# LightSwitch.net
KiCad netlist of a schematic drawn in EAGLE
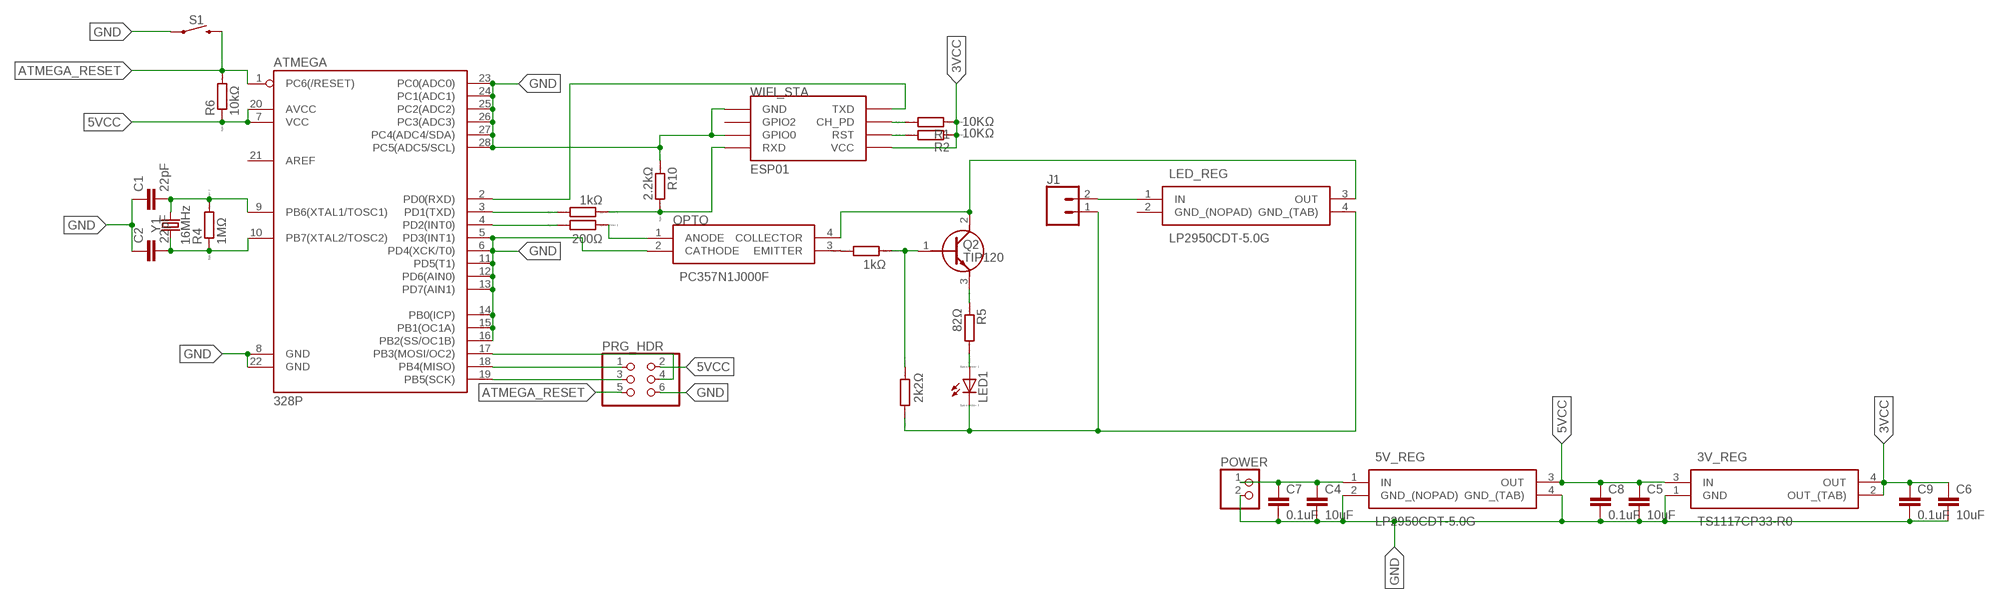
[diagram p0: schematic, sheet 1]

(export (version "E")
  (design (tool "Eeschema 10.0.6"))
  (components
    (comp (ref "3V_REG")
      (value "TS1117CP33-R0")
      (footprint "eagle-import:TO229P990X238-4N")
      (fields
        (field (name "MANUFACTURER_PART_NUMBER") "LP2950CDT-5.0G")
        (field (name "MOUSER_PART_NUMBER") "863-LP2950CDT-5.0G")
        (field (name "RS_PART_NUMBER") "0463593P")
      )
      (libsource (lib "eagle-import") (part "TS1117CP33-R0"))
    )
    (comp (ref "5V_REG")
      (value "LP2950CDT-5.0G")
      (footprint "eagle-import:TO229P990X238-4N")
      (fields
        (field (name "MOUSER_PART_NUMBER") "863-LP2950CDT-5.0G")
        (field (name "RS_PART_NUMBER") "0463593P")
      )
      (libsource (lib "eagle-import") (part "LP2950CDT-5.0G"))
    )
    (comp (ref "ATMEGA")
      (value "328P")
      (footprint "eagle-import:DIP28")
      (libsource (lib "eagle-import") (part "ATMEGA328P_PDIP"))
    )
    (comp (ref "C1")
      (value "22pF")
      (footprint "eagle-import:1206")
      (libsource (lib "eagle-import") (part "1.0UF-1206-50V-10%"))
    )
    (comp (ref "C2")
      (value "22pF")
      (footprint "eagle-import:1206")
      (libsource (lib "eagle-import") (part "1.0UF-1206-50V-10%"))
    )
    (comp (ref "C4")
      (value "10uF")
      (footprint "eagle-import:1206")
      (libsource (lib "eagle-import") (part "1.0UF-1206-50V-10%"))
    )
    (comp (ref "C5")
      (value "10uF")
      (footprint "eagle-import:1206")
      (libsource (lib "eagle-import") (part "1.0UF-1206-50V-10%"))
    )
    (comp (ref "C6")
      (value "10uF")
      (footprint "eagle-import:1206")
      (libsource (lib "eagle-import") (part "1.0UF-1206-50V-10%"))
    )
    (comp (ref "C7")
      (value "0.1uF")
      (footprint "eagle-import:1206")
      (libsource (lib "eagle-import") (part "1.0UF-1206-50V-10%"))
    )
    (comp (ref "C8")
      (value "0.1uF")
      (footprint "eagle-import:1206")
      (libsource (lib "eagle-import") (part "1.0UF-1206-50V-10%"))
    )
    (comp (ref "C9")
      (value "0.1uF")
      (footprint "eagle-import:1206")
      (libsource (lib "eagle-import") (part "1.0UF-1206-50V-10%"))
    )
    (comp (ref "J1")
      (value "CONN_025MM")
      (footprint "eagle-import:SCREWTERMINAL-5MM-2")
      (libsource (lib "eagle-import") (part "CONN_025MM"))
    )
    (comp (ref "LED1")
      (value "LED_ELD260")
      (footprint "eagle-import:LED_LD260")
      (libsource (lib "eagle-import") (part "LED_ELD260"))
    )
    (comp (ref "LED_REG")
      (value "LP2950CDT-5.0G")
      (footprint "eagle-import:TO229P990X238-4N")
      (fields
        (field (name "MOUSER_PART_NUMBER") "863-LP2950CDT-5.0G")
        (field (name "RS_PART_NUMBER") "0463593P")
      )
      (libsource (lib "eagle-import") (part "LP2950CDT-5.0G"))
    )
    (comp (ref "OPTO")
      (value "PC357N1J000F")
      (footprint "eagle-import:SOP254P675X300-4N")
      (fields
        (field (name "MOUSER_PART_NUMBER") "852-PC357N1J000F")
        (field (name "RS_PART_NUMBER") "1460767")
      )
      (libsource (lib "eagle-import") (part "PC357N1J000F"))
    )
    (comp (ref "POWER")
      (value "PINHD-1X2")
      (footprint "eagle-import:1X02")
      (libsource (lib "eagle-import") (part "PINHD-1X2"))
    )
    (comp (ref "PRG_HDR")
      (value "PINHD-2X3")
      (footprint "eagle-import:2X03")
      (libsource (lib "eagle-import") (part "PINHD-2X3"))
    )
    (comp (ref "Q2")
      (value "TIP120")
      (footprint "eagle-import:TO220")
      (fields (field (name "MOUSER_PART_NUMBER") "512-TIP120"))
      (libsource (lib "eagle-import") (part "TIP120"))
    )
    (comp (ref "R1")
      (value "10KΩ")
      (footprint "eagle-import:R1210")
      (libsource (lib "eagle-import") (part "RR1210"))
    )
    (comp (ref "R2")
      (value "10KΩ")
      (footprint "eagle-import:R1210")
      (libsource (lib "eagle-import") (part "RR1210"))
    )
    (comp (ref "R3")
      (value "200Ω")
      (footprint "eagle-import:R1210")
      (libsource (lib "eagle-import") (part "RR1210"))
    )
    (comp (ref "R4")
      (value "1MΩ")
      (footprint "eagle-import:R1210")
      (libsource (lib "eagle-import") (part "RR1210"))
    )
    (comp (ref "R5")
      (value "82Ω")
      (footprint "eagle-import:R1210")
      (libsource (lib "eagle-import") (part "RR1210"))
    )
    (comp (ref "R6")
      (value "10kΩ")
      (footprint "eagle-import:R1210")
      (libsource (lib "eagle-import") (part "RR1210"))
    )
    (comp (ref "R7")
      (value "1kΩ")
      (footprint "eagle-import:R1210")
      (libsource (lib "eagle-import") (part "RR1210"))
    )
    (comp (ref "R8")
      (value "2k2Ω")
      (footprint "eagle-import:R1210")
      (libsource (lib "eagle-import") (part "RR1210"))
    )
    (comp (ref "R9")
      (value "1kΩ")
      (footprint "eagle-import:R1210")
      (libsource (lib "eagle-import") (part "RR1210"))
    )
    (comp (ref "R10")
      (value "2.2kΩ")
      (footprint "eagle-import:R1210")
      (libsource (lib "eagle-import") (part "RR1210"))
    )
    (comp (ref "S1")
      (value "MOMENTARY-SWITCH-SPST-PTH-6.0MM")
      (footprint "eagle-import:TACTILE_SWITCH_PTH_6.0MM")
      (libsource (lib "eagle-import") (part "MOMENTARY-SWITCH-SPST-PTH-6.0MM"))
    )
    (comp (ref "WIFI_STA")
      (value "ESP01")
      (footprint "eagle-import:ESP01")
      (libsource (lib "eagle-import") (part "ESP01"))
    )
    (comp (ref "Y1")
      (value "16MHz")
      (footprint "eagle-import:HC49UP")
      (libsource (lib "eagle-import") (part "CRYSTAL-8MHZSMD-HC49UP"))
    )
  )
  (nets
    (net (code "1") (name "/GND_(NOPAD)") (class "Default")
      (node (ref "LED_REG") (pin "2") (pinfunction "GND_(NOPAD)_2") (pintype "power_in"))
    )
    (net (code "2") (name "3VCC") (class "Default")
      (node (ref "3V_REG") (pin "2") (pinfunction "OUT_(TAB)_2") (pintype "output"))
      (node (ref "3V_REG") (pin "4") (pinfunction "OUT_4") (pintype "output"))
      (node (ref "C6") (pin "1") (pinfunction "1_1") (pintype "passive"))
      (node (ref "C9") (pin "1") (pinfunction "1_1") (pintype "passive"))
      (node (ref "R1") (pin "1") (pinfunction "1_1") (pintype "passive"))
      (node (ref "R2") (pin "1") (pinfunction "1_1") (pintype "passive"))
      (node (ref "WIFI_STA") (pin "VCC") (pinfunction "VCC_VCC") (pintype "bidirectional"))
    )
    (net (code "3") (name "5VCC") (class "Default")
      (node (ref "3V_REG") (pin "3") (pinfunction "IN_3") (pintype "input"))
      (node (ref "5V_REG") (pin "3") (pinfunction "OUT_3") (pintype "output"))
      (node (ref "ATMEGA") (pin "20") (pinfunction "AVCC_20") (pintype "bidirectional"))
      (node (ref "ATMEGA") (pin "7") (pinfunction "VCC_7") (pintype "bidirectional"))
      (node (ref "C5") (pin "1") (pinfunction "1_1") (pintype "passive"))
      (node (ref "C8") (pin "1") (pinfunction "1_1") (pintype "passive"))
      (node (ref "PRG_HDR") (pin "2") (pinfunction "2_2") (pintype "passive"))
      (node (ref "R6") (pin "1") (pinfunction "1_1") (pintype "passive"))
    )
    (net (code "4") (name "ATMEGA_RESET") (class "Default")
      (node (ref "ATMEGA") (pin "1") (pinfunction "PC6(/RESET)_1") (pintype "bidirectional"))
      (node (ref "PRG_HDR") (pin "5") (pinfunction "5_5") (pintype "passive"))
      (node (ref "R6") (pin "2") (pinfunction "2_2") (pintype "passive"))
      (node (ref "S1") (pin "3") (pinfunction "2_3") (pintype "passive"))
    )
    (net (code "5") (name "GND") (class "Default")
      (node (ref "3V_REG") (pin "1") (pinfunction "GND_1") (pintype "power_in"))
      (node (ref "5V_REG") (pin "2") (pinfunction "GND_(NOPAD)_2") (pintype "power_in"))
      (node (ref "5V_REG") (pin "4") (pinfunction "GND_(TAB)_4") (pintype "power_in"))
      (node (ref "ATMEGA") (pin "11") (pinfunction "PD5(T1)_11") (pintype "bidirectional"))
      (node (ref "ATMEGA") (pin "12") (pinfunction "PD6(AIN0)_12") (pintype "bidirectional"))
      (node (ref "ATMEGA") (pin "13") (pinfunction "PD7(AIN1)_13") (pintype "bidirectional"))
      (node (ref "ATMEGA") (pin "14") (pinfunction "PB0(ICP)_14") (pintype "bidirectional"))
      (node (ref "ATMEGA") (pin "15") (pinfunction "PB1(OC1A)_15") (pintype "bidirectional"))
      (node (ref "ATMEGA") (pin "16") (pinfunction "PB2(SS/OC1B)_16") (pintype "bidirectional"))
      (node (ref "ATMEGA") (pin "22") (pinfunction "GND_22") (pintype "bidirectional"))
      (node (ref "ATMEGA") (pin "23") (pinfunction "PC0(ADC0)_23") (pintype "bidirectional"))
      (node (ref "ATMEGA") (pin "24") (pinfunction "PC1(ADC1)_24") (pintype "bidirectional"))
      (node (ref "ATMEGA") (pin "25") (pinfunction "PC2(ADC2)_25") (pintype "bidirectional"))
      (node (ref "ATMEGA") (pin "26") (pinfunction "PC3(ADC3)_26") (pintype "bidirectional"))
      (node (ref "ATMEGA") (pin "27") (pinfunction "PC4(ADC4/SDA)_27") (pintype "bidirectional"))
      (node (ref "ATMEGA") (pin "28") (pinfunction "PC5(ADC5/SCL)_28") (pintype "bidirectional"))
      (node (ref "ATMEGA") (pin "5") (pinfunction "PD3(INT1)_5") (pintype "bidirectional"))
      (node (ref "ATMEGA") (pin "6") (pinfunction "PD4(XCK/T0)_6") (pintype "bidirectional"))
      (node (ref "ATMEGA") (pin "8") (pinfunction "GND_8") (pintype "bidirectional"))
      (node (ref "C1") (pin "1") (pinfunction "1_1") (pintype "passive"))
      (node (ref "C2") (pin "1") (pinfunction "1_1") (pintype "passive"))
      (node (ref "C4") (pin "2") (pinfunction "2_2") (pintype "passive"))
      (node (ref "C5") (pin "2") (pinfunction "2_2") (pintype "passive"))
      (node (ref "C6") (pin "2") (pinfunction "2_2") (pintype "passive"))
      (node (ref "C7") (pin "2") (pinfunction "2_2") (pintype "passive"))
      (node (ref "C8") (pin "2") (pinfunction "2_2") (pintype "passive"))
      (node (ref "C9") (pin "2") (pinfunction "2_2") (pintype "passive"))
      (node (ref "OPTO") (pin "2") (pinfunction "CATHODE_2") (pintype "bidirectional"))
      (node (ref "POWER") (pin "2") (pinfunction "2_2") (pintype "passive"))
      (node (ref "PRG_HDR") (pin "6") (pinfunction "6_6") (pintype "passive"))
      (node (ref "R10") (pin "1") (pinfunction "1_1") (pintype "passive"))
      (node (ref "S1") (pin "1") (pinfunction "1_1") (pintype "passive"))
      (node (ref "WIFI_STA") (pin "GND") (pinfunction "GND_GND") (pintype "bidirectional"))
      (node (ref "WIFI_STA") (pin "GPIO0") (pinfunction "GPIO0_GPIO0") (pintype "bidirectional"))
    )
    (net (code "6") (name "Net-(5V_REG-IN)") (class "Default")
      (node (ref "5V_REG") (pin "1") (pinfunction "IN_1") (pintype "input"))
      (node (ref "C4") (pin "1") (pinfunction "1_1") (pintype "passive"))
      (node (ref "C7") (pin "1") (pinfunction "1_1") (pintype "passive"))
      (node (ref "POWER") (pin "1") (pinfunction "1_1") (pintype "passive"))
    )
    (net (code "7") (name "Net-(ATMEGA-PB3(MOSI{slash}OC2))") (class "Default")
      (node (ref "ATMEGA") (pin "17") (pinfunction "PB3(MOSI/OC2)_17") (pintype "bidirectional"))
      (node (ref "PRG_HDR") (pin "4") (pinfunction "4_4") (pintype "passive"))
    )
    (net (code "8") (name "Net-(ATMEGA-PB4(MISO))") (class "Default")
      (node (ref "ATMEGA") (pin "18") (pinfunction "PB4(MISO)_18") (pintype "bidirectional"))
      (node (ref "PRG_HDR") (pin "1") (pinfunction "1_1") (pintype "passive"))
    )
    (net (code "9") (name "Net-(ATMEGA-PB5(SCK))") (class "Default")
      (node (ref "ATMEGA") (pin "19") (pinfunction "PB5(SCK)_19") (pintype "bidirectional"))
      (node (ref "PRG_HDR") (pin "3") (pinfunction "3_3") (pintype "passive"))
    )
    (net (code "10") (name "Net-(ATMEGA-PB6(XTAL1{slash}TOSC1))") (class "Default")
      (node (ref "ATMEGA") (pin "9") (pinfunction "PB6(XTAL1/TOSC1)_9") (pintype "bidirectional"))
      (node (ref "C1") (pin "2") (pinfunction "2_2") (pintype "passive"))
      (node (ref "R4") (pin "2") (pinfunction "2_2") (pintype "passive"))
      (node (ref "Y1") (pin "2") (pinfunction "2_2") (pintype "passive"))
    )
    (net (code "11") (name "Net-(ATMEGA-PB7(XTAL2{slash}TOSC2))") (class "Default")
      (node (ref "ATMEGA") (pin "10") (pinfunction "PB7(XTAL2/TOSC2)_10") (pintype "bidirectional"))
      (node (ref "C2") (pin "2") (pinfunction "2_2") (pintype "passive"))
      (node (ref "R4") (pin "1") (pinfunction "1_1") (pintype "passive"))
      (node (ref "Y1") (pin "1") (pinfunction "1_1") (pintype "passive"))
    )
    (net (code "12") (name "Net-(ATMEGA-PD0(RXD))") (class "Default")
      (node (ref "ATMEGA") (pin "2") (pinfunction "PD0(RXD)_2") (pintype "bidirectional"))
      (node (ref "WIFI_STA") (pin "TX") (pinfunction "TXD_TX") (pintype "bidirectional"))
    )
    (net (code "13") (name "Net-(ATMEGA-PD1(TXD))") (class "Default")
      (node (ref "ATMEGA") (pin "3") (pinfunction "PD1(TXD)_3") (pintype "bidirectional"))
      (node (ref "R9") (pin "2") (pinfunction "2_2") (pintype "passive"))
    )
    (net (code "14") (name "Net-(ATMEGA-PD2(INT0))") (class "Default")
      (node (ref "ATMEGA") (pin "4") (pinfunction "PD2(INT0)_4") (pintype "bidirectional"))
      (node (ref "R3") (pin "2") (pinfunction "2_2") (pintype "passive"))
    )
    (net (code "15") (name "Net-(LED1-C)") (class "Default")
      (node (ref "J1") (pin "1") (pinfunction "1_1") (pintype "passive"))
      (node (ref "LED1") (pin "K") (pinfunction "C_K") (pintype "passive"))
      (node (ref "LED_REG") (pin "4") (pinfunction "GND_(TAB)_4") (pintype "power_in"))
      (node (ref "R8") (pin "2") (pinfunction "2_2") (pintype "passive"))
    )
    (net (code "16") (name "Net-(LED1-PadA)") (class "Default")
      (node (ref "LED1") (pin "A") (pinfunction "A_A") (pintype "passive"))
      (node (ref "R5") (pin "2") (pinfunction "2_2") (pintype "passive"))
    )
    (net (code "17") (name "Net-(LED_REG-IN)") (class "Default")
      (node (ref "J1") (pin "2") (pinfunction "2_2") (pintype "passive"))
      (node (ref "LED_REG") (pin "1") (pinfunction "IN_1") (pintype "input"))
    )
    (net (code "18") (name "Net-(LED_REG-OUT)") (class "Default")
      (node (ref "LED_REG") (pin "3") (pinfunction "OUT_3") (pintype "output"))
      (node (ref "OPTO") (pin "4") (pinfunction "COLLECTOR_4") (pintype "bidirectional"))
      (node (ref "Q2") (pin "2") (pinfunction "C_2") (pintype "bidirectional"))
    )
    (net (code "19") (name "Net-(OPTO-ANODE)") (class "Default")
      (node (ref "OPTO") (pin "1") (pinfunction "ANODE_1") (pintype "bidirectional"))
      (node (ref "R3") (pin "1") (pinfunction "1_1") (pintype "passive"))
    )
    (net (code "20") (name "Net-(OPTO-EMITTER)") (class "Default")
      (node (ref "OPTO") (pin "3") (pinfunction "EMITTER_3") (pintype "bidirectional"))
      (node (ref "R7") (pin "2") (pinfunction "2_2") (pintype "passive"))
    )
    (net (code "21") (name "Net-(Q2-B)") (class "Default")
      (node (ref "Q2") (pin "1") (pinfunction "B_1") (pintype "bidirectional"))
      (node (ref "R7") (pin "1") (pinfunction "1_1") (pintype "passive"))
      (node (ref "R8") (pin "1") (pinfunction "1_1") (pintype "passive"))
    )
    (net (code "22") (name "Net-(Q2-E)") (class "Default")
      (node (ref "Q2") (pin "3") (pinfunction "E_3") (pintype "bidirectional"))
      (node (ref "R5") (pin "1") (pinfunction "1_1") (pintype "passive"))
    )
    (net (code "23") (name "Net-(R1-Pad2)") (class "Default")
      (node (ref "R1") (pin "2") (pinfunction "2_2") (pintype "passive"))
      (node (ref "WIFI_STA") (pin "CH_PD") (pinfunction "CH_PD_CH_PD") (pintype "bidirectional"))
    )
    (net (code "24") (name "Net-(R2-Pad2)") (class "Default")
      (node (ref "R2") (pin "2") (pinfunction "2_2") (pintype "passive"))
      (node (ref "WIFI_STA") (pin "RST") (pinfunction "RST_RST") (pintype "bidirectional"))
    )
    (net (code "25") (name "Net-(WIFI_STA-RXD)") (class "Default")
      (node (ref "R10") (pin "2") (pinfunction "2_2") (pintype "passive"))
      (node (ref "R9") (pin "1") (pinfunction "1_1") (pintype "passive"))
      (node (ref "WIFI_STA") (pin "RX") (pinfunction "RXD_RX") (pintype "bidirectional"))
    )
    (net (code "26") (name "unconnected-(ATMEGA-AREF-Pad21)") (class "Default")
      (node (ref "ATMEGA") (pin "21") (pinfunction "AREF_21") (pintype "bidirectional"))
    )
    (net (code "27") (name "unconnected-(WIFI_STA-PadGPIO2)") (class "Default")
      (node (ref "WIFI_STA") (pin "GPIO2") (pinfunction "GPIO2_GPIO2") (pintype "bidirectional"))
    )
  )
)
